# Power_Distribution_-_Rear_Turn_and_Brake.net
KiCad netlist of a schematic drawn in Altium Designer
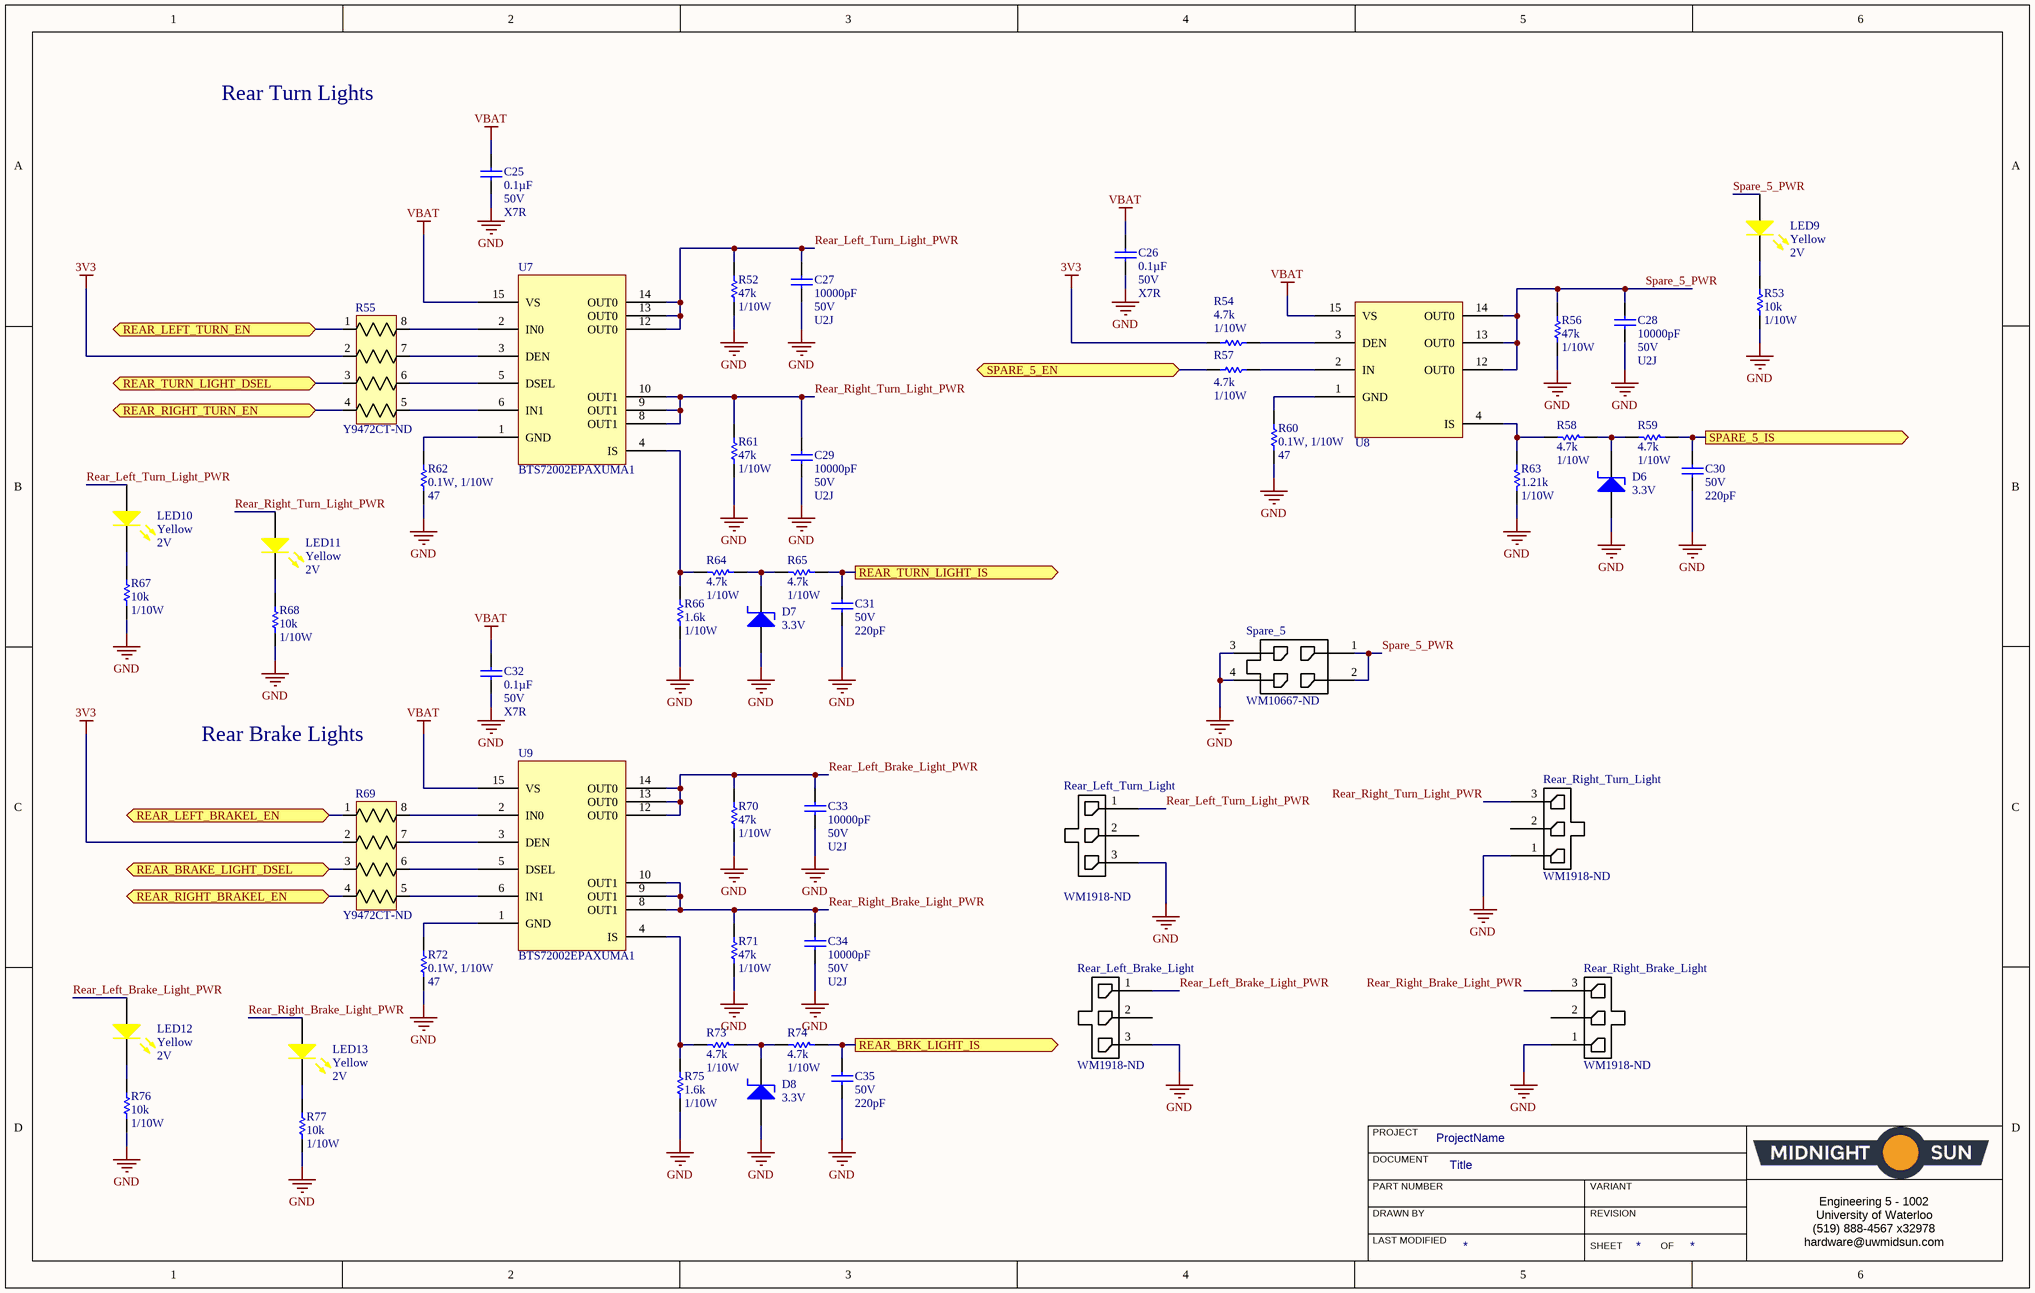
[diagram p0: Power Distribution - Rear Turn and Brake Lights.SchDoc]

(export (version "E")
  (design (tool "Eeschema 10.0.6"))
  (components
    (comp (ref "C25")
      (value "CAP CER 0.1UF 50V 10% X7R 0603")
      (footprint "CAP, 0603")
      (description "0.10µF ±10% 50V Ceramic Capacitor X7R 0603 (1608 Metric)")
      (fields
        (field (name "TOLERANCE") "±10%")
        (field (name "CAPACITANCE") "0.1µF")
        (field (name "VOLTAGE") "50V")
        (field (name "TEMPERATURE COEFFICIENT") "X7R")
      )
      (libsource (lib "Schematic Diagrams") (part "CAP CER 0.1UF 50V 10% X7R 0603"))
    )
    (comp (ref "C26")
      (value "CAP CER 0.1UF 50V 10% X7R 0603")
      (footprint "CAP, 0603")
      (description "0.10µF ±10% 50V Ceramic Capacitor X7R 0603 (1608 Metric)")
      (fields
        (field (name "TOLERANCE") "±10%")
        (field (name "CAPACITANCE") "0.1µF")
        (field (name "VOLTAGE") "50V")
        (field (name "TEMPERATURE COEFFICIENT") "X7R")
      )
      (libsource (lib "Schematic Diagrams") (part "CAP CER 0.1UF 50V 10% X7R 0603"))
    )
    (comp (ref "C27")
      (value "CAP CER 10nF 50V 5% X7R 0603")
      (footprint "CAP, 0603")
      (description "10000pF ±5% 50V Ceramic Capacitor U2J 0603 (1608 Metric)")
      (fields
        (field (name "TOLERANCE") "±5%")
        (field (name "CAPACITANCE") "10000pF")
        (field (name "VOLTAGE") "50V")
        (field (name "TEMPERATURE COEFFICIENT") "U2J")
      )
      (libsource (lib "Schematic Diagrams") (part "CAP CER 10nF 50V 5% X7R 0603"))
    )
    (comp (ref "C28")
      (value "CAP CER 10nF 50V 5% X7R 0603")
      (footprint "CAP, 0603")
      (description "10000pF ±5% 50V Ceramic Capacitor U2J 0603 (1608 Metric)")
      (fields
        (field (name "TOLERANCE") "±5%")
        (field (name "CAPACITANCE") "10000pF")
        (field (name "VOLTAGE") "50V")
        (field (name "TEMPERATURE COEFFICIENT") "U2J")
      )
      (libsource (lib "Schematic Diagrams") (part "CAP CER 10nF 50V 5% X7R 0603"))
    )
    (comp (ref "C29")
      (value "CAP CER 10nF 50V 5% X7R 0603")
      (footprint "CAP, 0603")
      (description "10000pF ±5% 50V Ceramic Capacitor U2J 0603 (1608 Metric)")
      (fields
        (field (name "TOLERANCE") "±5%")
        (field (name "CAPACITANCE") "10000pF")
        (field (name "VOLTAGE") "50V")
        (field (name "TEMPERATURE COEFFICIENT") "U2J")
      )
      (libsource (lib "Schematic Diagrams") (part "CAP CER 10nF 50V 5% X7R 0603"))
    )
    (comp (ref "C30")
      (value "CAP CER 220PF 50V C0G/NP0 0603")
      (footprint "CAP, 0603")
      (description "220pF ±5% 50V Ceramic Capacitor C0G, NP0 0603 (1608 Metric)")
      (fields
        (field (name "MANUFACTURER") "KEMET")
        (field (name "TOLERANCE") "5%")
        (field (name "VOLTAGE RATING") "50V")
        (field (name "CAPACITANCE") "220pF")
      )
      (libsource (lib "Schematic Diagrams") (part "CAP CER 220PF 50V C0G/NP0 0603"))
    )
    (comp (ref "C31")
      (value "CAP CER 220PF 50V C0G/NP0 0603")
      (footprint "CAP, 0603")
      (description "220pF ±5% 50V Ceramic Capacitor C0G, NP0 0603 (1608 Metric)")
      (fields
        (field (name "MANUFACTURER") "KEMET")
        (field (name "TOLERANCE") "5%")
        (field (name "VOLTAGE RATING") "50V")
        (field (name "CAPACITANCE") "220pF")
      )
      (libsource (lib "Schematic Diagrams") (part "CAP CER 220PF 50V C0G/NP0 0603"))
    )
    (comp (ref "C32")
      (value "CAP CER 0.1UF 50V 10% X7R 0603")
      (footprint "CAP, 0603")
      (description "0.10µF ±10% 50V Ceramic Capacitor X7R 0603 (1608 Metric)")
      (fields
        (field (name "TOLERANCE") "±10%")
        (field (name "CAPACITANCE") "0.1µF")
        (field (name "VOLTAGE") "50V")
        (field (name "TEMPERATURE COEFFICIENT") "X7R")
      )
      (libsource (lib "Schematic Diagrams") (part "CAP CER 0.1UF 50V 10% X7R 0603"))
    )
    (comp (ref "C33")
      (value "CAP CER 10nF 50V 5% X7R 0603")
      (footprint "CAP, 0603")
      (description "10000pF ±5% 50V Ceramic Capacitor U2J 0603 (1608 Metric)")
      (fields
        (field (name "TOLERANCE") "±5%")
        (field (name "CAPACITANCE") "10000pF")
        (field (name "VOLTAGE") "50V")
        (field (name "TEMPERATURE COEFFICIENT") "U2J")
      )
      (libsource (lib "Schematic Diagrams") (part "CAP CER 10nF 50V 5% X7R 0603"))
    )
    (comp (ref "C34")
      (value "CAP CER 10nF 50V 5% X7R 0603")
      (footprint "CAP, 0603")
      (description "10000pF ±5% 50V Ceramic Capacitor U2J 0603 (1608 Metric)")
      (fields
        (field (name "TOLERANCE") "±5%")
        (field (name "CAPACITANCE") "10000pF")
        (field (name "VOLTAGE") "50V")
        (field (name "TEMPERATURE COEFFICIENT") "U2J")
      )
      (libsource (lib "Schematic Diagrams") (part "CAP CER 10nF 50V 5% X7R 0603"))
    )
    (comp (ref "C35")
      (value "CAP CER 220PF 50V C0G/NP0 0603")
      (footprint "CAP, 0603")
      (description "220pF ±5% 50V Ceramic Capacitor C0G, NP0 0603 (1608 Metric)")
      (fields
        (field (name "MANUFACTURER") "KEMET")
        (field (name "TOLERANCE") "5%")
        (field (name "VOLTAGE RATING") "50V")
        (field (name "CAPACITANCE") "220pF")
      )
      (libsource (lib "Schematic Diagrams") (part "CAP CER 220PF 50V C0G/NP0 0603"))
    )
    (comp (ref "D6")
      (value "DIODE ZENER 3.3V 200MW SOD323")
      (footprint "sod-323")
      (description "Zener Diode 3.3V 200mW ±5% Surface Mount SOD-323")
      (fields (field (name "VOLTAGE") "3.3V"))
      (libsource (lib "Schematic Diagrams") (part "DIODE ZENER 3.3V 200MW SOD323"))
    )
    (comp (ref "D7")
      (value "DIODE ZENER 3.3V 200MW SOD323")
      (footprint "sod-323")
      (description "Zener Diode 3.3V 200mW ±5% Surface Mount SOD-323")
      (fields (field (name "VOLTAGE") "3.3V"))
      (libsource (lib "Schematic Diagrams") (part "DIODE ZENER 3.3V 200MW SOD323"))
    )
    (comp (ref "D8")
      (value "DIODE ZENER 3.3V 200MW SOD323")
      (footprint "sod-323")
      (description "Zener Diode 3.3V 200mW ±5% Surface Mount SOD-323")
      (fields (field (name "VOLTAGE") "3.3V"))
      (libsource (lib "Schematic Diagrams") (part "DIODE ZENER 3.3V 200MW SOD323"))
    )
    (comp (ref "LED9")
      (value "LED YELLOW CLEAR 2.1V 0603")
      (footprint "LED_0603")
      (description "Yellow 590nm LED Indication - Discrete 2V 0603 (1608 Metric)")
      (fields
        (field (name "MANUFACTURER") "Wurth Electronics Inc.")
        (field (name "MANUFACTURER PART NUMBER") "150060YS75000")
        (field (name "COLOR") "Yellow")
        (field (name "VOLTAGE - FORWARD (VF) (TYP)") "2V")
      )
      (libsource (lib "Schematic Diagrams") (part "LED YELLOW CLEAR 2.1V 0603"))
    )
    (comp (ref "LED10")
      (value "LED YELLOW CLEAR 2.1V 0603")
      (footprint "LED_0603")
      (description "Yellow 590nm LED Indication - Discrete 2V 0603 (1608 Metric)")
      (fields
        (field (name "MANUFACTURER") "Wurth Electronics Inc.")
        (field (name "MANUFACTURER PART NUMBER") "150060YS75000")
        (field (name "COLOR") "Yellow")
        (field (name "VOLTAGE - FORWARD (VF) (TYP)") "2V")
      )
      (libsource (lib "Schematic Diagrams") (part "LED YELLOW CLEAR 2.1V 0603"))
    )
    (comp (ref "LED11")
      (value "LED YELLOW CLEAR 2.1V 0603")
      (footprint "LED_0603")
      (description "Yellow 590nm LED Indication - Discrete 2V 0603 (1608 Metric)")
      (fields
        (field (name "MANUFACTURER") "Wurth Electronics Inc.")
        (field (name "MANUFACTURER PART NUMBER") "150060YS75000")
        (field (name "COLOR") "Yellow")
        (field (name "VOLTAGE - FORWARD (VF) (TYP)") "2V")
      )
      (libsource (lib "Schematic Diagrams") (part "LED YELLOW CLEAR 2.1V 0603"))
    )
    (comp (ref "LED12")
      (value "LED YELLOW CLEAR 2.1V 0603")
      (footprint "LED_0603")
      (description "Yellow 590nm LED Indication - Discrete 2V 0603 (1608 Metric)")
      (fields
        (field (name "MANUFACTURER") "Wurth Electronics Inc.")
        (field (name "MANUFACTURER PART NUMBER") "150060YS75000")
        (field (name "COLOR") "Yellow")
        (field (name "VOLTAGE - FORWARD (VF) (TYP)") "2V")
      )
      (libsource (lib "Schematic Diagrams") (part "LED YELLOW CLEAR 2.1V 0603"))
    )
    (comp (ref "LED13")
      (value "LED YELLOW CLEAR 2.1V 0603")
      (footprint "LED_0603")
      (description "Yellow 590nm LED Indication - Discrete 2V 0603 (1608 Metric)")
      (fields
        (field (name "MANUFACTURER") "Wurth Electronics Inc.")
        (field (name "MANUFACTURER PART NUMBER") "150060YS75000")
        (field (name "COLOR") "Yellow")
        (field (name "VOLTAGE - FORWARD (VF) (TYP)") "2V")
      )
      (libsource (lib "Schematic Diagrams") (part "LED YELLOW CLEAR 2.1V 0603"))
    )
    (comp (ref "R52")
      (value "RES 47K OHM 1% 1/10W 0603")
      (footprint "RES, 0603")
      (description "47 kOhms ±1% 0.1W, 1/10W Chip Resistor 0603 (1608 Metric) Automotive AEC-Q200 Thick Film")
      (fields
        (field (name "MANUFACTURER") "Panasonic")
        (field (name "MANUFACTURER PART NUMBER") "ERJ3EKF4702V")
        (field (name "RESISTANCE") "47k")
        (field (name "POWER RATING") "1/10W")
      )
      (libsource (lib "Schematic Diagrams") (part "RES 47K OHM 1% 1/10W 0603"))
    )
    (comp (ref "R53")
      (value "RES 10K OHM 1% 1/10W 0603")
      (footprint "RES, 0603")
      (description "RES SMD 10K OHM 1% 1/10W 0603")
      (fields
        (field (name "TOLERANCE") "±1%")
        (field (name "RESISTANCE") "10k")
        (field (name "POWER") "1/10W")
      )
      (libsource (lib "Schematic Diagrams") (part "RES 10K OHM 1% 1/10W 0603"))
    )
    (comp (ref "R54")
      (value "RES 4.7K OHM 1% 1/10W 0603")
      (footprint "RES, 0603")
      (description "4.7k Ohm ±1% 0.1W, 1/10W Chip Resistor 0603 (1608 Metric) Moisture Resistant Thick Film")
      (fields
        (field (name "TOLERANCE") "±1%")
        (field (name "RESISTANCE (OHMS)") "4.7k")
        (field (name "POWER (WATTS)") "1/10W")
      )
      (libsource (lib "Schematic Diagrams") (part "RES 4.7K OHM 1% 1/10W 0603"))
    )
    (comp (ref "R55")
      (value "RES ARRAY 4 RES 4.7K OHM 1206")
      (footprint "RES ARRAY 4RES 1206")
      (fields (field (name "TOLERANCE") "±5%") (field (name "SUPPLIER PART NUMBER 1") "Y9472CT-ND"))
      (libsource (lib "Schematic Diagrams") (part "RES ARRAY 4 RES 4.7K OHM 1206"))
    )
    (comp (ref "R56")
      (value "RES 47K OHM 1% 1/10W 0603")
      (footprint "RES, 0603")
      (description "47 kOhms ±1% 0.1W, 1/10W Chip Resistor 0603 (1608 Metric) Automotive AEC-Q200 Thick Film")
      (fields
        (field (name "MANUFACTURER") "Panasonic")
        (field (name "MANUFACTURER PART NUMBER") "ERJ3EKF4702V")
        (field (name "RESISTANCE") "47k")
        (field (name "POWER RATING") "1/10W")
      )
      (libsource (lib "Schematic Diagrams") (part "RES 47K OHM 1% 1/10W 0603"))
    )
    (comp (ref "R57")
      (value "RES 4.7K OHM 1% 1/10W 0603")
      (footprint "RES, 0603")
      (description "4.7k Ohm ±1% 0.1W, 1/10W Chip Resistor 0603 (1608 Metric) Moisture Resistant Thick Film")
      (fields
        (field (name "TOLERANCE") "±1%")
        (field (name "RESISTANCE (OHMS)") "4.7k")
        (field (name "POWER (WATTS)") "1/10W")
      )
      (libsource (lib "Schematic Diagrams") (part "RES 4.7K OHM 1% 1/10W 0603"))
    )
    (comp (ref "R58")
      (value "RES 4.7K OHM 1% 1/10W 0603")
      (footprint "RES, 0603")
      (description "4.7k Ohm ±1% 0.1W, 1/10W Chip Resistor 0603 (1608 Metric) Moisture Resistant Thick Film")
      (fields
        (field (name "TOLERANCE") "±1%")
        (field (name "RESISTANCE (OHMS)") "4.7k")
        (field (name "POWER (WATTS)") "1/10W")
      )
      (libsource (lib "Schematic Diagrams") (part "RES 4.7K OHM 1% 1/10W 0603"))
    )
    (comp (ref "R59")
      (value "RES 4.7K OHM 1% 1/10W 0603")
      (footprint "RES, 0603")
      (description "4.7k Ohm ±1% 0.1W, 1/10W Chip Resistor 0603 (1608 Metric) Moisture Resistant Thick Film")
      (fields
        (field (name "TOLERANCE") "±1%")
        (field (name "RESISTANCE (OHMS)") "4.7k")
        (field (name "POWER (WATTS)") "1/10W")
      )
      (libsource (lib "Schematic Diagrams") (part "RES 4.7K OHM 1% 1/10W 0603"))
    )
    (comp (ref "R60")
      (value "RES SMD 47 OHM 1% 1/10W 0603")
      (footprint "RES, 0603")
      (fields
        (field (name "TOLERANCE") "±1%")
        (field (name "POWER (WATTS)") "0.1W, 1/10W")
        (field (name "VALUES") "47")
      )
      (libsource (lib "Schematic Diagrams") (part "RES SMD 47 OHM 1% 1/10W 0603"))
    )
    (comp (ref "R61")
      (value "RES 47K OHM 1% 1/10W 0603")
      (footprint "RES, 0603")
      (description "47 kOhms ±1% 0.1W, 1/10W Chip Resistor 0603 (1608 Metric) Automotive AEC-Q200 Thick Film")
      (fields
        (field (name "MANUFACTURER") "Panasonic")
        (field (name "MANUFACTURER PART NUMBER") "ERJ3EKF4702V")
        (field (name "RESISTANCE") "47k")
        (field (name "POWER RATING") "1/10W")
      )
      (libsource (lib "Schematic Diagrams") (part "RES 47K OHM 1% 1/10W 0603"))
    )
    (comp (ref "R62")
      (value "RES SMD 47 OHM 1% 1/10W 0603")
      (footprint "RES, 0603")
      (fields
        (field (name "TOLERANCE") "±1%")
        (field (name "POWER (WATTS)") "0.1W, 1/10W")
        (field (name "VALUES") "47")
      )
      (libsource (lib "Schematic Diagrams") (part "RES SMD 47 OHM 1% 1/10W 0603"))
    )
    (comp (ref "R63")
      (value "RES 1.21K OHM 1% 1/10W 0603")
      (footprint "RES, 0603")
      (description "1.21k Ohm ±1% 0.1W, 1/10W Chip Resistor 0603 (1608 Metric) Moisture Resistant Thick Film")
      (fields
        (field (name "TOLERANCE") "±1%")
        (field (name "RESISTANCE") "1.21k")
        (field (name "POWER") "1/10W")
      )
      (libsource (lib "Schematic Diagrams") (part "RES 1.21K OHM 1% 1/10W 0603"))
    )
    (comp (ref "R64")
      (value "RES 4.7K OHM 1% 1/10W 0603")
      (footprint "RES, 0603")
      (description "4.7k Ohm ±1% 0.1W, 1/10W Chip Resistor 0603 (1608 Metric) Moisture Resistant Thick Film")
      (fields
        (field (name "TOLERANCE") "±1%")
        (field (name "RESISTANCE (OHMS)") "4.7k")
        (field (name "POWER (WATTS)") "1/10W")
      )
      (libsource (lib "Schematic Diagrams") (part "RES 4.7K OHM 1% 1/10W 0603"))
    )
    (comp (ref "R65")
      (value "RES 4.7K OHM 1% 1/10W 0603")
      (footprint "RES, 0603")
      (description "4.7k Ohm ±1% 0.1W, 1/10W Chip Resistor 0603 (1608 Metric) Moisture Resistant Thick Film")
      (fields
        (field (name "TOLERANCE") "±1%")
        (field (name "RESISTANCE (OHMS)") "4.7k")
        (field (name "POWER (WATTS)") "1/10W")
      )
      (libsource (lib "Schematic Diagrams") (part "RES 4.7K OHM 1% 1/10W 0603"))
    )
    (comp (ref "R66")
      (value "RES 1.6K OHM 1% 1/10W 0603")
      (footprint "RES, 0603")
      (description "1.6 kOhms ±1% 0.1W, 1/10W Chip Resistor 0603 (1608 Metric) Moisture Resistant Thick Film")
      (fields
        (field (name "MANUFACTURER") "Yageo")
        (field (name "MANUFACTURER PART NUMBER") "RC0603FR-071K6L")
        (field (name "RESISTANCE") "1.6k")
        (field (name "POWER RATING") "1/10W")
      )
      (libsource (lib "Schematic Diagrams") (part "RES 1.6K OHM 1% 1/10W 0603"))
    )
    (comp (ref "R67")
      (value "RES 10K OHM 1% 1/10W 0603")
      (footprint "RES, 0603")
      (description "RES SMD 10K OHM 1% 1/10W 0603")
      (fields
        (field (name "TOLERANCE") "±1%")
        (field (name "RESISTANCE") "10k")
        (field (name "POWER") "1/10W")
      )
      (libsource (lib "Schematic Diagrams") (part "RES 10K OHM 1% 1/10W 0603"))
    )
    (comp (ref "R68")
      (value "RES 10K OHM 1% 1/10W 0603")
      (footprint "RES, 0603")
      (description "RES SMD 10K OHM 1% 1/10W 0603")
      (fields
        (field (name "TOLERANCE") "±1%")
        (field (name "RESISTANCE") "10k")
        (field (name "POWER") "1/10W")
      )
      (libsource (lib "Schematic Diagrams") (part "RES 10K OHM 1% 1/10W 0603"))
    )
    (comp (ref "R69")
      (value "RES ARRAY 4 RES 4.7K OHM 1206")
      (footprint "RES ARRAY 4RES 1206")
      (fields (field (name "TOLERANCE") "±5%") (field (name "SUPPLIER PART NUMBER 1") "Y9472CT-ND"))
      (libsource (lib "Schematic Diagrams") (part "RES ARRAY 4 RES 4.7K OHM 1206"))
    )
    (comp (ref "R70")
      (value "RES 47K OHM 1% 1/10W 0603")
      (footprint "RES, 0603")
      (description "47 kOhms ±1% 0.1W, 1/10W Chip Resistor 0603 (1608 Metric) Automotive AEC-Q200 Thick Film")
      (fields
        (field (name "MANUFACTURER") "Panasonic")
        (field (name "MANUFACTURER PART NUMBER") "ERJ3EKF4702V")
        (field (name "RESISTANCE") "47k")
        (field (name "POWER RATING") "1/10W")
      )
      (libsource (lib "Schematic Diagrams") (part "RES 47K OHM 1% 1/10W 0603"))
    )
    (comp (ref "R71")
      (value "RES 47K OHM 1% 1/10W 0603")
      (footprint "RES, 0603")
      (description "47 kOhms ±1% 0.1W, 1/10W Chip Resistor 0603 (1608 Metric) Automotive AEC-Q200 Thick Film")
      (fields
        (field (name "MANUFACTURER") "Panasonic")
        (field (name "MANUFACTURER PART NUMBER") "ERJ3EKF4702V")
        (field (name "RESISTANCE") "47k")
        (field (name "POWER RATING") "1/10W")
      )
      (libsource (lib "Schematic Diagrams") (part "RES 47K OHM 1% 1/10W 0603"))
    )
    (comp (ref "R72")
      (value "RES SMD 47 OHM 1% 1/10W 0603")
      (footprint "RES, 0603")
      (fields
        (field (name "TOLERANCE") "±1%")
        (field (name "POWER (WATTS)") "0.1W, 1/10W")
        (field (name "VALUES") "47")
      )
      (libsource (lib "Schematic Diagrams") (part "RES SMD 47 OHM 1% 1/10W 0603"))
    )
    (comp (ref "R73")
      (value "RES 4.7K OHM 1% 1/10W 0603")
      (footprint "RES, 0603")
      (description "4.7k Ohm ±1% 0.1W, 1/10W Chip Resistor 0603 (1608 Metric) Moisture Resistant Thick Film")
      (fields
        (field (name "TOLERANCE") "±1%")
        (field (name "RESISTANCE (OHMS)") "4.7k")
        (field (name "POWER (WATTS)") "1/10W")
      )
      (libsource (lib "Schematic Diagrams") (part "RES 4.7K OHM 1% 1/10W 0603"))
    )
    (comp (ref "R74")
      (value "RES 4.7K OHM 1% 1/10W 0603")
      (footprint "RES, 0603")
      (description "4.7k Ohm ±1% 0.1W, 1/10W Chip Resistor 0603 (1608 Metric) Moisture Resistant Thick Film")
      (fields
        (field (name "TOLERANCE") "±1%")
        (field (name "RESISTANCE (OHMS)") "4.7k")
        (field (name "POWER (WATTS)") "1/10W")
      )
      (libsource (lib "Schematic Diagrams") (part "RES 4.7K OHM 1% 1/10W 0603"))
    )
    (comp (ref "R75")
      (value "RES 1.6K OHM 1% 1/10W 0603")
      (footprint "RES, 0603")
      (description "1.6 kOhms ±1% 0.1W, 1/10W Chip Resistor 0603 (1608 Metric) Moisture Resistant Thick Film")
      (fields
        (field (name "MANUFACTURER") "Yageo")
        (field (name "MANUFACTURER PART NUMBER") "RC0603FR-071K6L")
        (field (name "RESISTANCE") "1.6k")
        (field (name "POWER RATING") "1/10W")
      )
      (libsource (lib "Schematic Diagrams") (part "RES 1.6K OHM 1% 1/10W 0603"))
    )
    (comp (ref "R76")
      (value "RES 10K OHM 1% 1/10W 0603")
      (footprint "RES, 0603")
      (description "RES SMD 10K OHM 1% 1/10W 0603")
      (fields
        (field (name "TOLERANCE") "±1%")
        (field (name "RESISTANCE") "10k")
        (field (name "POWER") "1/10W")
      )
      (libsource (lib "Schematic Diagrams") (part "RES 10K OHM 1% 1/10W 0603"))
    )
    (comp (ref "R77")
      (value "RES 10K OHM 1% 1/10W 0603")
      (footprint "RES, 0603")
      (description "RES SMD 10K OHM 1% 1/10W 0603")
      (fields
        (field (name "TOLERANCE") "±1%")
        (field (name "RESISTANCE") "10k")
        (field (name "POWER") "1/10W")
      )
      (libsource (lib "Schematic Diagrams") (part "RES 10K OHM 1% 1/10W 0603"))
    )
    (comp (ref "Rear_Left_Brake_Light")
      (value "CONN 3POS MICROFIT")
      (footprint "CONN, 3 POS MICROFIT")
      (description "Connector Header Through Hole 3 position 0.118\" (3.00mm)")
      (fields (field (name "SUPPLIER PART NUMBER 1") "WM1918-ND"))
      (libsource (lib "Schematic Diagrams") (part "CONN 3POS MICROFIT"))
    )
    (comp (ref "Rear_Left_Turn_Light")
      (value "CONN 3POS MICROFIT")
      (footprint "CONN, 3 POS MICROFIT")
      (description "Connector Header Through Hole 3 position 0.118\" (3.00mm)")
      (fields (field (name "SUPPLIER PART NUMBER 1") "WM1918-ND"))
      (libsource (lib "Schematic Diagrams") (part "CONN 3POS MICROFIT"))
    )
    (comp (ref "Rear_Right_Brake_Light")
      (value "CONN 3POS MICROFIT")
      (footprint "CONN, 3 POS MICROFIT")
      (description "Connector Header Through Hole 3 position 0.118\" (3.00mm)")
      (fields (field (name "SUPPLIER PART NUMBER 1") "WM1918-ND"))
      (libsource (lib "Schematic Diagrams") (part "CONN 3POS MICROFIT"))
    )
    (comp (ref "Rear_Right_Turn_Light")
      (value "CONN 3POS MICROFIT")
      (footprint "CONN, 3 POS MICROFIT")
      (description "Connector Header Through Hole 3 position 0.118\" (3.00mm)")
      (fields (field (name "SUPPLIER PART NUMBER 1") "WM1918-ND"))
      (libsource (lib "Schematic Diagrams") (part "CONN 3POS MICROFIT"))
    )
    (comp (ref "Spare_5")
      (value "CONN 4POS MICRO-FIT 3mm")
      (footprint "CONN 4POS MICROFIT (2x2)")
      (fields
        (field (name "MANUFACTURER") "Molex, LLC")
        (field (name "MANUFACTURER PART NUMBER") "430450427")
        (field (name "SUPPLIER PART NUMBER 1") "WM10667-ND")
      )
      (libsource (lib "Schematic Diagrams") (part "CONN 4POS MICRO-FIT 3mm"))
    )
    (comp (ref "U7")
      (value "IC LOAD SWITCH BTS7200-2EPA PG-TSDSO-14_1")
      (footprint "IC LOAD SWITCH PG-TSDSO-14-22")
      (description "Power Switch/Driver 1:1 N-Channel 1.2A PG-TSDSO-14-22")
      (fields
        (field (name "MANUFACTURER") "Infineon")
        (field (name "MANUFACTURER PART NUMBER") "BTS72002EPAXUMA1")
      )
      (libsource (lib "Schematic Diagrams") (part "IC LOAD SWITCH BTS7200-2EPA PG-TSDSO-14_1"))
    )
    (comp (ref "U8")
      (value "IC LOAD SWITCH BTS70401EPA PG-TSDSO-14-22")
      (footprint "IC LOAD SWITCH PG-TSDSO-14-22")
      (description "Power Switch/Driver 1:1 N-Channel 4.5A PG-TSDSO-14-22")
      (fields
        (field (name "MANUFACTURER") "Infineon")
        (field (name "MANUFACTURER PART NUMBER") "BTS70401EPAXUMA1")
      )
      (libsource (lib "Schematic Diagrams") (part "IC LOAD SWITCH BTS70401EPA PG-TSDSO-14-22"))
    )
    (comp (ref "U9")
      (value "IC LOAD SWITCH BTS7200-2EPA PG-TSDSO-14_1")
      (footprint "IC LOAD SWITCH PG-TSDSO-14-22")
      (description "Power Switch/Driver 1:1 N-Channel 1.2A PG-TSDSO-14-22")
      (fields
        (field (name "MANUFACTURER") "Infineon")
        (field (name "MANUFACTURER PART NUMBER") "BTS72002EPAXUMA1")
      )
      (libsource (lib "Schematic Diagrams") (part "IC LOAD SWITCH BTS7200-2EPA PG-TSDSO-14_1"))
    )
  )
  (nets
    (net (code "1") (name "/REAR_BRAKE_LIGHT_DSEL") (class "Default")
      (node (ref "R69") (pin "3") (pinfunction "3_3") (pintype "passive"))
    )
    (net (code "2") (name "/REAR_BRK_LIGHT_IS") (class "Default")
      (node (ref "C35") (pin "1") (pinfunction "1_1") (pintype "passive"))
      (node (ref "R74") (pin "1") (pinfunction "1_1") (pintype "passive"))
    )
    (net (code "3") (name "/REAR_LEFT_BRAKEL_EN") (class "Default")
      (node (ref "R69") (pin "1") (pinfunction "1_1") (pintype "passive"))
    )
    (net (code "4") (name "/REAR_LEFT_TURN_EN") (class "Default")
      (node (ref "R55") (pin "1") (pinfunction "1_1") (pintype "passive"))
    )
    (net (code "5") (name "/REAR_RIGHT_BRAKEL_EN") (class "Default")
      (node (ref "R69") (pin "4") (pinfunction "4_4") (pintype "passive"))
    )
    (net (code "6") (name "/REAR_RIGHT_TURN_EN") (class "Default")
      (node (ref "R55") (pin "4") (pinfunction "4_4") (pintype "passive"))
    )
    (net (code "7") (name "/REAR_TURN_LIGHT_DSEL") (class "Default")
      (node (ref "R55") (pin "3") (pinfunction "3_3") (pintype "passive"))
    )
    (net (code "8") (name "/REAR_TURN_LIGHT_IS") (class "Default")
      (node (ref "C31") (pin "1") (pinfunction "1_1") (pintype "passive"))
      (node (ref "R65") (pin "1") (pinfunction "1_1") (pintype "passive"))
    )
    (net (code "9") (name "/Rear_Left_Brake_Light_PWR") (class "Default")
      (node (ref "C33") (pin "1") (pinfunction "1_1") (pintype "passive"))
      (node (ref "LED12") (pin "1") (pinfunction "A_1") (pintype "passive"))
      (node (ref "R70") (pin "1") (pinfunction "1_1") (pintype "passive"))
      (node (ref "Rear_Left_Brake_Light") (pin "1") (pinfunction "1_1") (pintype "passive"))
      (node (ref "U9") (pin "12") (pinfunction "OUT0_12") (pintype "passive"))
      (node (ref "U9") (pin "13") (pinfunction "OUT0_13") (pintype "passive"))
      (node (ref "U9") (pin "14") (pinfunction "OUT0_14") (pintype "passive"))
    )
    (net (code "10") (name "/Rear_Left_Turn_Light_PWR") (class "Default")
      (node (ref "C27") (pin "1") (pinfunction "1_1") (pintype "passive"))
      (node (ref "LED10") (pin "1") (pinfunction "A_1") (pintype "passive"))
      (node (ref "R52") (pin "1") (pinfunction "1_1") (pintype "passive"))
      (node (ref "Rear_Left_Turn_Light") (pin "1") (pinfunction "1_1") (pintype "passive"))
      (node (ref "U7") (pin "12") (pinfunction "OUT0_12") (pintype "passive"))
      (node (ref "U7") (pin "13") (pinfunction "OUT0_13") (pintype "passive"))
      (node (ref "U7") (pin "14") (pinfunction "OUT0_14") (pintype "passive"))
    )
    (net (code "11") (name "/Rear_Right_Brake_Light_PWR") (class "Default")
      (node (ref "C34") (pin "1") (pinfunction "1_1") (pintype "passive"))
      (node (ref "LED13") (pin "1") (pinfunction "A_1") (pintype "passive"))
      (node (ref "R71") (pin "1") (pinfunction "1_1") (pintype "passive"))
      (node (ref "Rear_Right_Brake_Light") (pin "3") (pinfunction "3_3") (pintype "passive"))
      (node (ref "U9") (pin "10") (pinfunction "OUT1_10") (pintype "passive"))
      (node (ref "U9") (pin "8") (pinfunction "OUT1_8") (pintype "passive"))
      (node (ref "U9") (pin "9") (pinfunction "OUT1_9") (pintype "passive"))
    )
    (net (code "12") (name "/Rear_Right_Turn_Light_PWR") (class "Default")
      (node (ref "C29") (pin "1") (pinfunction "1_1") (pintype "passive"))
      (node (ref "LED11") (pin "1") (pinfunction "A_1") (pintype "passive"))
      (node (ref "R61") (pin "1") (pinfunction "1_1") (pintype "passive"))
      (node (ref "Rear_Right_Turn_Light") (pin "3") (pinfunction "3_3") (pintype "passive"))
      (node (ref "U7") (pin "10") (pinfunction "OUT1_10") (pintype "passive"))
      (node (ref "U7") (pin "8") (pinfunction "OUT1_8") (pintype "passive"))
      (node (ref "U7") (pin "9") (pinfunction "OUT1_9") (pintype "passive"))
    )
    (net (code "13") (name "/SPARE_5_EN") (class "Default")
      (node (ref "R57") (pin "1") (pinfunction "1_1") (pintype "passive"))
    )
    (net (code "14") (name "/SPARE_5_IS") (class "Default")
      (node (ref "C30") (pin "1") (pinfunction "1_1") (pintype "passive"))
      (node (ref "R59") (pin "1") (pinfunction "1_1") (pintype "passive"))
    )
    (net (code "15") (name "/Spare_5_PWR") (class "Default")
      (node (ref "C28") (pin "1") (pinfunction "1_1") (pintype "passive"))
      (node (ref "LED9") (pin "1") (pinfunction "A_1") (pintype "passive"))
      (node (ref "R56") (pin "1") (pinfunction "1_1") (pintype "passive"))
      (node (ref "Spare_5") (pin "1") (pinfunction "1_1") (pintype "passive"))
      (node (ref "Spare_5") (pin "2") (pinfunction "2_2") (pintype "passive"))
      (node (ref "U8") (pin "12") (pinfunction "OUT0_12") (pintype "passive"))
      (node (ref "U8") (pin "13") (pinfunction "OUT0_13") (pintype "passive"))
      (node (ref "U8") (pin "14") (pinfunction "OUT0_14") (pintype "passive"))
    )
    (net (code "16") (name "3V3") (class "Default")
      (node (ref "R54") (pin "1") (pinfunction "1_1") (pintype "passive"))
      (node (ref "R55") (pin "2") (pinfunction "2_2") (pintype "passive"))
      (node (ref "R69") (pin "2") (pinfunction "2_2") (pintype "passive"))
    )
    (net (code "17") (name "GND") (class "Default")
      (node (ref "C25") (pin "2") (pinfunction "2_2") (pintype "passive"))
      (node (ref "C26") (pin "2") (pinfunction "2_2") (pintype "passive"))
      (node (ref "C27") (pin "2") (pinfunction "2_2") (pintype "passive"))
      (node (ref "C28") (pin "2") (pinfunction "2_2") (pintype "passive"))
      (node (ref "C29") (pin "2") (pinfunction "2_2") (pintype "passive"))
      (node (ref "C30") (pin "2") (pinfunction "2_2") (pintype "passive"))
      (node (ref "C31") (pin "2") (pinfunction "2_2") (pintype "passive"))
      (node (ref "C32") (pin "2") (pinfunction "2_2") (pintype "passive"))
      (node (ref "C33") (pin "2") (pinfunction "2_2") (pintype "passive"))
      (node (ref "C34") (pin "2") (pinfunction "2_2") (pintype "passive"))
      (node (ref "C35") (pin "2") (pinfunction "2_2") (pintype "passive"))
      (node (ref "D6") (pin "1") (pinfunction "A_1") (pintype "passive"))
      (node (ref "D7") (pin "1") (pinfunction "A_1") (pintype "passive"))
      (node (ref "D8") (pin "1") (pinfunction "A_1") (pintype "passive"))
      (node (ref "R52") (pin "2") (pinfunction "2_2") (pintype "passive"))
      (node (ref "R53") (pin "2") (pinfunction "2_2") (pintype "passive"))
      (node (ref "R56") (pin "2") (pinfunction "2_2") (pintype "passive"))
      (node (ref "R60") (pin "2") (pinfunction "2_2") (pintype "passive"))
      (node (ref "R61") (pin "2") (pinfunction "2_2") (pintype "passive"))
      (node (ref "R62") (pin "2") (pinfunction "2_2") (pintype "passive"))
      (node (ref "R63") (pin "2") (pinfunction "2_2") (pintype "passive"))
      (node (ref "R66") (pin "2") (pinfunction "2_2") (pintype "passive"))
      (node (ref "R67") (pin "2") (pinfunction "2_2") (pintype "passive"))
      (node (ref "R68") (pin "2") (pinfunction "2_2") (pintype "passive"))
      (node (ref "R70") (pin "2") (pinfunction "2_2") (pintype "passive"))
      (node (ref "R71") (pin "2") (pinfunction "2_2") (pintype "passive"))
      (node (ref "R72") (pin "2") (pinfunction "2_2") (pintype "passive"))
      (node (ref "R75") (pin "2") (pinfunction "2_2") (pintype "passive"))
      (node (ref "R76") (pin "2") (pinfunction "2_2") (pintype "passive"))
      (node (ref "R77") (pin "2") (pinfunction "2_2") (pintype "passive"))
      (node (ref "Rear_Left_Brake_Light") (pin "3") (pinfunction "3_3") (pintype "passive"))
      (node (ref "Rear_Left_Turn_Light") (pin "3") (pinfunction "3_3") (pintype "passive"))
      (node (ref "Rear_Right_Brake_Light") (pin "1") (pinfunction "1_1") (pintype "passive"))
      (node (ref "Rear_Right_Turn_Light") (pin "1") (pinfunction "1_1") (pintype "passive"))
      (node (ref "Spare_5") (pin "3") (pinfunction "3_3") (pintype "passive"))
      (node (ref "Spare_5") (pin "4") (pinfunction "4_4") (pintype "passive"))
    )
    (net (code "18") (name "Net-(D6-K)") (class "Default")
      (node (ref "D6") (pin "2") (pinfunction "K_2") (pintype "passive"))
      (node (ref "R58") (pin "1") (pinfunction "1_1") (pintype "passive"))
      (node (ref "R59") (pin "2") (pinfunction "2_2") (pintype "passive"))
    )
    (net (code "19") (name "Net-(D7-K)") (class "Default")
      (node (ref "D7") (pin "2") (pinfunction "K_2") (pintype "passive"))
      (node (ref "R64") (pin "1") (pinfunction "1_1") (pintype "passive"))
      (node (ref "R65") (pin "2") (pinfunction "2_2") (pintype "passive"))
    )
    (net (code "20") (name "Net-(D8-K)") (class "Default")
      (node (ref "D8") (pin "2") (pinfunction "K_2") (pintype "passive"))
      (node (ref "R73") (pin "1") (pinfunction "1_1") (pintype "passive"))
      (node (ref "R74") (pin "2") (pinfunction "2_2") (pintype "passive"))
    )
    (net (code "21") (name "Net-(LED9-K)") (class "Default")
      (node (ref "LED9") (pin "2") (pinfunction "K_2") (pintype "passive"))
      (node (ref "R53") (pin "1") (pinfunction "1_1") (pintype "passive"))
    )
    (net (code "22") (name "Net-(LED10-K)") (class "Default")
      (node (ref "LED10") (pin "2") (pinfunction "K_2") (pintype "passive"))
      (node (ref "R67") (pin "1") (pinfunction "1_1") (pintype "passive"))
    )
    (net (code "23") (name "Net-(LED11-K)") (class "Default")
      (node (ref "LED11") (pin "2") (pinfunction "K_2") (pintype "passive"))
      (node (ref "R68") (pin "1") (pinfunction "1_1") (pintype "passive"))
    )
    (net (code "24") (name "Net-(LED12-K)") (class "Default")
      (node (ref "LED12") (pin "2") (pinfunction "K_2") (pintype "passive"))
      (node (ref "R76") (pin "1") (pinfunction "1_1") (pintype "passive"))
    )
    (net (code "25") (name "Net-(LED13-K)") (class "Default")
      (node (ref "LED13") (pin "2") (pinfunction "K_2") (pintype "passive"))
      (node (ref "R77") (pin "1") (pinfunction "1_1") (pintype "passive"))
    )
    (net (code "26") (name "Net-(U7-DEN)") (class "Default")
      (node (ref "R55") (pin "7") (pinfunction "7_7") (pintype "passive"))
      (node (ref "U7") (pin "3") (pinfunction "DEN_3") (pintype "passive"))
    )
    (net (code "27") (name "Net-(U7-DSEL)") (class "Default")
      (node (ref "R55") (pin "6") (pinfunction "6_6") (pintype "passive"))
      (node (ref "U7") (pin "5") (pinfunction "DSEL_5") (pintype "passive"))
    )
    (net (code "28") (name "Net-(U7-GND)") (class "Default")
      (node (ref "R62") (pin "1") (pinfunction "1_1") (pintype "passive"))
      (node (ref "U7") (pin "1") (pinfunction "GND_1") (pintype "passive"))
    )
    (net (code "29") (name "Net-(U7-IN0)") (class "Default")
      (node (ref "R55") (pin "8") (pinfunction "8_8") (pintype "passive"))
      (node (ref "U7") (pin "2") (pinfunction "IN0_2") (pintype "passive"))
    )
    (net (code "30") (name "Net-(U7-IN1)") (class "Default")
      (node (ref "R55") (pin "5") (pinfunction "5_5") (pintype "passive"))
      (node (ref "U7") (pin "6") (pinfunction "IN1_6") (pintype "passive"))
    )
    (net (code "31") (name "Net-(U7-IS)") (class "Default")
      (node (ref "R64") (pin "2") (pinfunction "2_2") (pintype "passive"))
      (node (ref "R66") (pin "1") (pinfunction "1_1") (pintype "passive"))
      (node (ref "U7") (pin "4") (pinfunction "IS_4") (pintype "passive"))
    )
    (net (code "32") (name "Net-(U8-DEN)") (class "Default")
      (node (ref "R54") (pin "2") (pinfunction "2_2") (pintype "passive"))
      (node (ref "U8") (pin "3") (pinfunction "DEN_3") (pintype "passive"))
    )
    (net (code "33") (name "Net-(U8-GND)") (class "Default")
      (node (ref "R60") (pin "1") (pinfunction "1_1") (pintype "passive"))
      (node (ref "U8") (pin "1") (pinfunction "GND_1") (pintype "passive"))
    )
    (net (code "34") (name "Net-(U8-IN)") (class "Default")
      (node (ref "R57") (pin "2") (pinfunction "2_2") (pintype "passive"))
      (node (ref "U8") (pin "2") (pinfunction "IN_2") (pintype "passive"))
    )
    (net (code "35") (name "Net-(U8-IS)") (class "Default")
      (node (ref "R58") (pin "2") (pinfunction "2_2") (pintype "passive"))
      (node (ref "R63") (pin "1") (pinfunction "1_1") (pintype "passive"))
      (node (ref "U8") (pin "4") (pinfunction "IS_4") (pintype "passive"))
    )
    (net (code "36") (name "Net-(U9-DEN)") (class "Default")
      (node (ref "R69") (pin "7") (pinfunction "7_7") (pintype "passive"))
      (node (ref "U9") (pin "3") (pinfunction "DEN_3") (pintype "passive"))
    )
    (net (code "37") (name "Net-(U9-DSEL)") (class "Default")
      (node (ref "R69") (pin "6") (pinfunction "6_6") (pintype "passive"))
      (node (ref "U9") (pin "5") (pinfunction "DSEL_5") (pintype "passive"))
    )
    (net (code "38") (name "Net-(U9-GND)") (class "Default")
      (node (ref "R72") (pin "1") (pinfunction "1_1") (pintype "passive"))
      (node (ref "U9") (pin "1") (pinfunction "GND_1") (pintype "passive"))
    )
    (net (code "39") (name "Net-(U9-IN0)") (class "Default")
      (node (ref "R69") (pin "8") (pinfunction "8_8") (pintype "passive"))
      (node (ref "U9") (pin "2") (pinfunction "IN0_2") (pintype "passive"))
    )
    (net (code "40") (name "Net-(U9-IN1)") (class "Default")
      (node (ref "R69") (pin "5") (pinfunction "5_5") (pintype "passive"))
      (node (ref "U9") (pin "6") (pinfunction "IN1_6") (pintype "passive"))
    )
    (net (code "41") (name "Net-(U9-IS)") (class "Default")
      (node (ref "R73") (pin "2") (pinfunction "2_2") (pintype "passive"))
      (node (ref "R75") (pin "1") (pinfunction "1_1") (pintype "passive"))
      (node (ref "U9") (pin "4") (pinfunction "IS_4") (pintype "passive"))
    )
    (net (code "42") (name "VBAT") (class "Default")
      (node (ref "C25") (pin "1") (pinfunction "1_1") (pintype "passive"))
      (node (ref "C26") (pin "1") (pinfunction "1_1") (pintype "passive"))
      (node (ref "C32") (pin "1") (pinfunction "1_1") (pintype "passive"))
      (node (ref "U7") (pin "15") (pinfunction "VS_15") (pintype "passive"))
      (node (ref "U8") (pin "15") (pinfunction "VS_15") (pintype "passive"))
      (node (ref "U9") (pin "15") (pinfunction "VS_15") (pintype "passive"))
    )
    (net (code "43") (name "unconnected-(Rear_Left_Brake_Light-21-Pad2)") (class "Default")
      (node (ref "Rear_Left_Brake_Light") (pin "2") (pinfunction "21_2") (pintype "passive"))
    )
    (net (code "44") (name "unconnected-(Rear_Left_Turn_Light-21-Pad2)") (class "Default")
      (node (ref "Rear_Left_Turn_Light") (pin "2") (pinfunction "21_2") (pintype "passive"))
    )
    (net (code "45") (name "unconnected-(Rear_Right_Brake_Light-21-Pad2)") (class "Default")
      (node (ref "Rear_Right_Brake_Light") (pin "2") (pinfunction "21_2") (pintype "passive"))
    )
    (net (code "46") (name "unconnected-(Rear_Right_Turn_Light-21-Pad2)") (class "Default")
      (node (ref "Rear_Right_Turn_Light") (pin "2") (pinfunction "21_2") (pintype "passive"))
    )
  )
)
